# LPCB234_-_PSU.net
KiCad netlist of a schematic drawn in Altium Designer
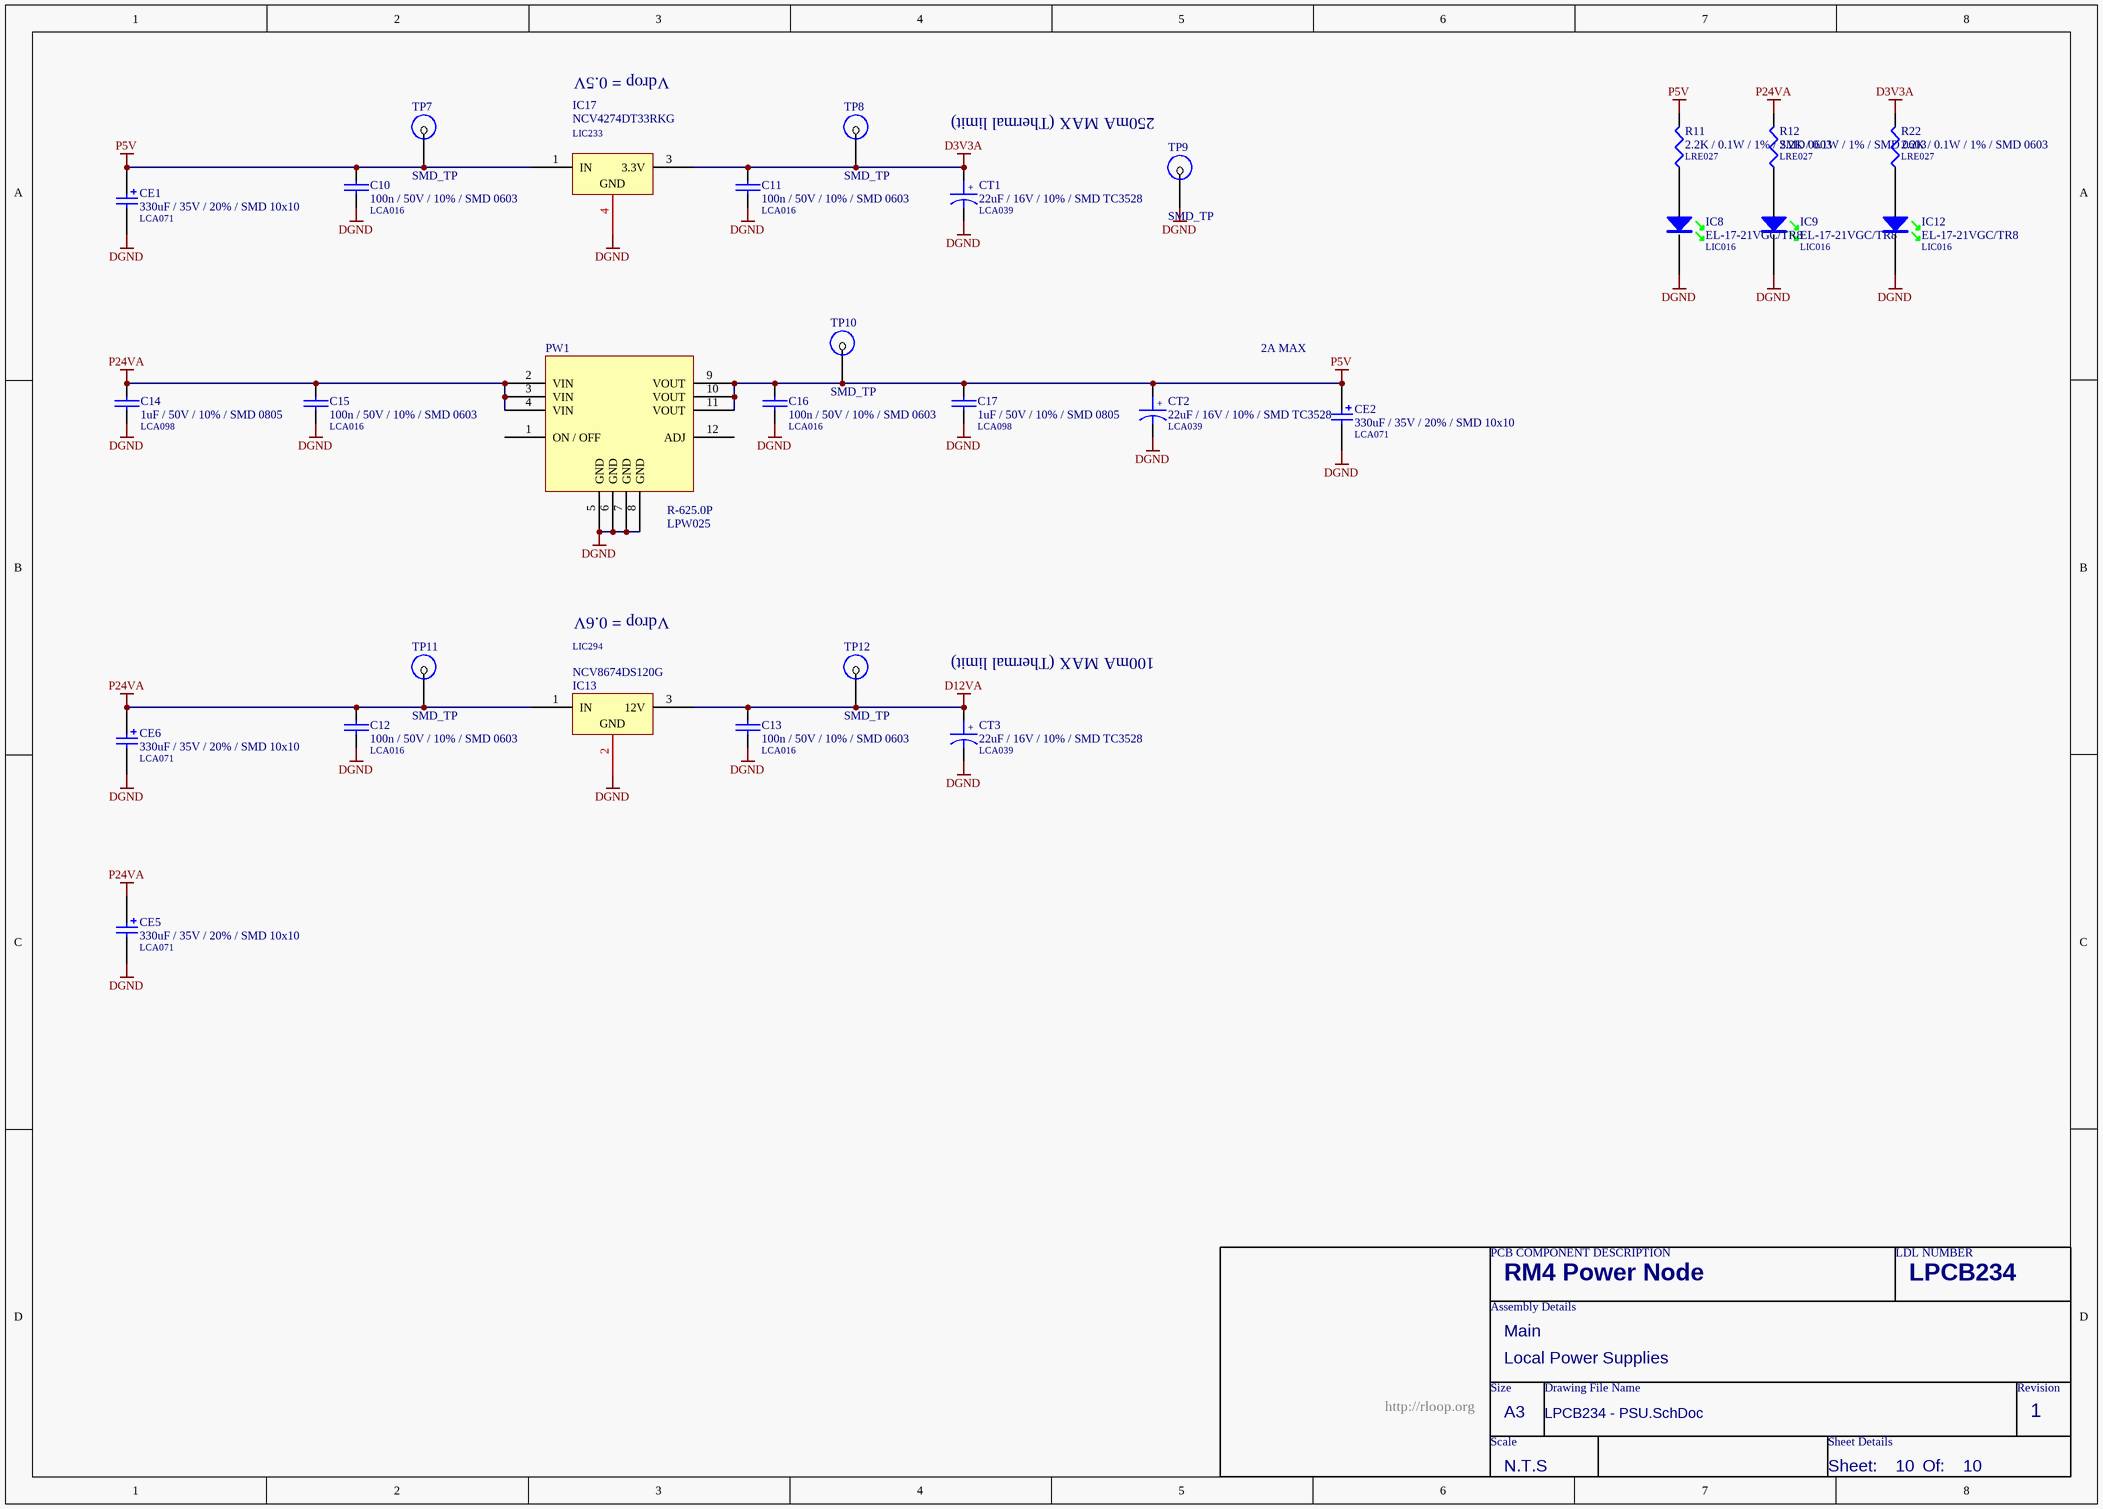
[diagram p0: LPCB234 - PSU.SchDoc]

(export (version "E")
  (design (tool "Eeschema 10.0.6"))
  (components
    (comp (ref "C10")
      (value "100n / 50V / 10% / SMD 0603")
      (footprint "LFP011__CC1608-0603-IPC7351_B")
      (description "Capacitor, Ceramic Chip, 100nF (0.1uF), 50V, 5%, SMD 0603 [LCA016]")
      (fields (field (name "LDL_NUMBER") "LCA016"))
      (libsource (lib "LDL_Capacitors") (part "100n / 50V / 10% / SMD 0603"))
    )
    (comp (ref "C11")
      (value "100n / 50V / 10% / SMD 0603")
      (footprint "LFP011__CC1608-0603-IPC7351_B")
      (description "Capacitor, Ceramic Chip, 100nF (0.1uF), 50V, 5%, SMD 0603 [LCA016]")
      (fields (field (name "LDL_NUMBER") "LCA016"))
      (libsource (lib "LDL_Capacitors") (part "100n / 50V / 10% / SMD 0603"))
    )
    (comp (ref "C12")
      (value "100n / 50V / 10% / SMD 0603")
      (footprint "LFP011__CC1608-0603-IPC7351_B")
      (description "Capacitor, Ceramic Chip, 100nF (0.1uF), 50V, 5%, SMD 0603 [LCA016]")
      (fields (field (name "LDL_NUMBER") "LCA016"))
      (libsource (lib "LDL_Capacitors") (part "100n / 50V / 10% / SMD 0603"))
    )
    (comp (ref "C13")
      (value "100n / 50V / 10% / SMD 0603")
      (footprint "LFP011__CC1608-0603-IPC7351_B")
      (description "Capacitor, Ceramic Chip, 100nF (0.1uF), 50V, 5%, SMD 0603 [LCA016]")
      (fields (field (name "LDL_NUMBER") "LCA016"))
      (libsource (lib "LDL_Capacitors") (part "100n / 50V / 10% / SMD 0603"))
    )
    (comp (ref "C14")
      (value "1uF / 50V / 10% / SMD 0805")
      (footprint "LFP010__CC2012-0805-IPC7351_B")
      (description "Capacitor, Ceramic Chip, 1uF, 50V, SMD 0805 [LCA098]")
      (fields (field (name "LDL_NUMBER") "LCA098"))
      (libsource (lib "LDL_Capacitors") (part "1uF / 50V / 10% / SMD 0805"))
    )
    (comp (ref "C15")
      (value "100n / 50V / 10% / SMD 0603")
      (footprint "LFP011__CC1608-0603-IPC7351_B")
      (description "Capacitor, Ceramic Chip, 100nF (0.1uF), 50V, 5%, SMD 0603 [LCA016]")
      (fields (field (name "LDL_NUMBER") "LCA016"))
      (libsource (lib "LDL_Capacitors") (part "100n / 50V / 10% / SMD 0603"))
    )
    (comp (ref "C16")
      (value "100n / 50V / 10% / SMD 0603")
      (footprint "LFP011__CC1608-0603-IPC7351_B")
      (description "Capacitor, Ceramic Chip, 100nF (0.1uF), 50V, 5%, SMD 0603 [LCA016]")
      (fields (field (name "LDL_NUMBER") "LCA016"))
      (libsource (lib "LDL_Capacitors") (part "100n / 50V / 10% / SMD 0603"))
    )
    (comp (ref "C17")
      (value "1uF / 50V / 10% / SMD 0805")
      (footprint "LFP010__CC2012-0805-IPC7351_B")
      (description "Capacitor, Ceramic Chip, 1uF, 50V, SMD 0805 [LCA098]")
      (fields (field (name "LDL_NUMBER") "LCA098"))
      (libsource (lib "LDL_Capacitors") (part "1uF / 50V / 10% / SMD 0805"))
    )
    (comp (ref "CE1")
      (value "330uF / 35V / 20% / SMD 10x10")
      (footprint "LFP041__NICHICON_WT_10X10")
      (description "Capacitor, Aluminum Electrolytic, 330uF, 35V, 20%, SMD (10mm x 10mm) [LCA071]")
      (fields (field (name "LDL_NUMBER") "LCA071"))
      (libsource (lib "LDL_Capacitors") (part "330uF / 35V / 20% / SMD 10x10"))
    )
    (comp (ref "CE2")
      (value "330uF / 35V / 20% / SMD 10x10")
      (footprint "LFP041__NICHICON_WT_10X10")
      (description "Capacitor, Aluminum Electrolytic, 330uF, 35V, 20%, SMD (10mm x 10mm) [LCA071]")
      (fields (field (name "LDL_NUMBER") "LCA071"))
      (libsource (lib "LDL_Capacitors") (part "330uF / 35V / 20% / SMD 10x10"))
    )
    (comp (ref "CE5")
      (value "330uF / 35V / 20% / SMD 10x10")
      (footprint "LFP041__NICHICON_WT_10X10")
      (description "Capacitor, Aluminum Electrolytic, 330uF, 35V, 20%, SMD (10mm x 10mm) [LCA071]")
      (fields (field (name "LDL_NUMBER") "LCA071"))
      (libsource (lib "LDL_Capacitors") (part "330uF / 35V / 20% / SMD 10x10"))
    )
    (comp (ref "CE6")
      (value "330uF / 35V / 20% / SMD 10x10")
      (footprint "LFP041__NICHICON_WT_10X10")
      (description "Capacitor, Aluminum Electrolytic, 330uF, 35V, 20%, SMD (10mm x 10mm) [LCA071]")
      (fields (field (name "LDL_NUMBER") "LCA071"))
      (libsource (lib "LDL_Capacitors") (part "330uF / 35V / 20% / SMD 10x10"))
    )
    (comp (ref "CT1")
      (value "22uF / 16V / 10% / SMD TC3528")
      (footprint "LFP018__TC3528")
      (description "Capacitor, Tantalum, 22uF, 16V, 10%, SMD TC3528 (BCASE) [LCA039]")
      (fields (field (name "LDL_NUMBER") "LCA039"))
      (libsource (lib "LDL_Capacitors") (part "22uF / 16V / 10% / SMD TC3528"))
    )
    (comp (ref "CT2")
      (value "22uF / 16V / 10% / SMD TC3528")
      (footprint "LFP018__TC3528")
      (description "Capacitor, Tantalum, 22uF, 16V, 10%, SMD TC3528 (BCASE) [LCA039]")
      (fields (field (name "LDL_NUMBER") "LCA039"))
      (libsource (lib "LDL_Capacitors") (part "22uF / 16V / 10% / SMD TC3528"))
    )
    (comp (ref "CT3")
      (value "22uF / 16V / 10% / SMD TC3528")
      (footprint "LFP018__TC3528")
      (description "Capacitor, Tantalum, 22uF, 16V, 10%, SMD TC3528 (BCASE) [LCA039]")
      (fields (field (name "LDL_NUMBER") "LCA039"))
      (libsource (lib "LDL_Capacitors") (part "22uF / 16V / 10% / SMD TC3528"))
    )
    (comp (ref "IC8")
      (value "EL-17-21VGC/TR8")
      (footprint "CR2012-0805-LED")
      (description "LED, SMD, 0805 Green [LIC016]")
      (fields (field (name "LDL_NUMBER") "LIC016"))
      (libsource (lib "LDL_Semiconductors") (part "EL-17-21VGC/TR8"))
    )
    (comp (ref "IC9")
      (value "EL-17-21VGC/TR8")
      (footprint "CR2012-0805-LED")
      (description "LED, SMD, 0805 Green [LIC016]")
      (fields (field (name "LDL_NUMBER") "LIC016"))
      (libsource (lib "LDL_Semiconductors") (part "EL-17-21VGC/TR8"))
    )
    (comp (ref "IC12")
      (value "EL-17-21VGC/TR8")
      (footprint "CR2012-0805-LED")
      (description "LED, SMD, 0805 Green [LIC016]")
      (fields (field (name "LDL_NUMBER") "LIC016"))
      (libsource (lib "LDL_Semiconductors") (part "EL-17-21VGC/TR8"))
    )
    (comp (ref "IC13")
      (value "NCV8674DS120G")
      (footprint "LFP082__D2PAK")
      (description "IC, Voltage Regulator, 0.35A, 12V, SMD D2PAK [LIC294]")
      (fields (field (name "LDL_NUMBER") "LIC294"))
      (libsource (lib "LDL_Semiconductors") (part "NCV8674DS120G"))
    )
    (comp (ref "IC17")
      (value "NCV4274DT33RKG")
      (footprint "LFP019__369A-13")
      (description "IC, Voltage Regulator, 400mA, 3.3V LDO, SMD DPAK [LIC233]")
      (fields (field (name "LDL_NUMBER") "LIC233"))
      (libsource (lib "LDL_Semiconductors") (part "NCV4274DT33RKG"))
    )
    (comp (ref "PW1")
      (value "R-625.0P")
      (footprint "R-625.0P")
      (description "Non Isolated DC/DC Module")
      (fields (field (name "LDL_NUMBER") "LPW025"))
      (libsource (lib "LDL_Power") (part "R-625.0P"))
    )
    (comp (ref "R11")
      (value "2.2K / 0.1W / 1% / SMD 0603")
      (footprint "LFP020__CR1608-0603-IPC7351_B")
      (description "Resistor, Ceramic Chip, 2.2K, 0.1W, 1%, SMD 0603 [LRE027]")
      (fields (field (name "LDL_NUMBER") "LRE027"))
      (libsource (lib "LDL_Resistors") (part "2.2K / 0.1W / 1% / SMD 0603"))
    )
    (comp (ref "R12")
      (value "2.2K / 0.1W / 1% / SMD 0603")
      (footprint "LFP020__CR1608-0603-IPC7351_B")
      (description "Resistor, Ceramic Chip, 2.2K, 0.1W, 1%, SMD 0603 [LRE027]")
      (fields (field (name "LDL_NUMBER") "LRE027"))
      (libsource (lib "LDL_Resistors") (part "2.2K / 0.1W / 1% / SMD 0603"))
    )
    (comp (ref "R22")
      (value "2.2K / 0.1W / 1% / SMD 0603")
      (footprint "LFP020__CR1608-0603-IPC7351_B")
      (description "Resistor, Ceramic Chip, 2.2K, 0.1W, 1%, SMD 0603 [LRE027]")
      (fields (field (name "LDL_NUMBER") "LRE027"))
      (libsource (lib "LDL_Resistors") (part "2.2K / 0.1W / 1% / SMD 0603"))
    )
    (comp (ref "TP7")
      (value "SMD_TP")
      (footprint "SMD-TP")
      (description "SMD Test Point")
      (libsource (lib "LDL_Connectors") (part "SMD_TP"))
    )
    (comp (ref "TP8")
      (value "SMD_TP")
      (footprint "SMD-TP")
      (description "SMD Test Point")
      (libsource (lib "LDL_Connectors") (part "SMD_TP"))
    )
    (comp (ref "TP9")
      (value "SMD_TP")
      (footprint "SMD-TP")
      (description "SMD Test Point")
      (libsource (lib "LDL_Connectors") (part "SMD_TP"))
    )
    (comp (ref "TP10")
      (value "SMD_TP")
      (footprint "SMD-TP")
      (description "SMD Test Point")
      (libsource (lib "LDL_Connectors") (part "SMD_TP"))
    )
    (comp (ref "TP11")
      (value "SMD_TP")
      (footprint "SMD-TP")
      (description "SMD Test Point")
      (libsource (lib "LDL_Connectors") (part "SMD_TP"))
    )
    (comp (ref "TP12")
      (value "SMD_TP")
      (footprint "SMD-TP")
      (description "SMD Test Point")
      (libsource (lib "LDL_Connectors") (part "SMD_TP"))
    )
  )
  (nets
    (net (code "1") (name "D3V3A") (class "Default")
      (node (ref "C11") (pin "1") (pintype "passive"))
      (node (ref "CT1") (pin "1") (pinfunction "1_1") (pintype "passive"))
      (node (ref "IC17") (pin "3") (pinfunction "3.3V_3") (pintype "power_in"))
      (node (ref "R22") (pin "2") (pintype "passive"))
      (node (ref "TP8") (pin "1") (pintype "passive"))
    )
    (net (code "2") (name "D12VA") (class "Default")
      (node (ref "C13") (pin "1") (pintype "passive"))
      (node (ref "CT3") (pin "1") (pinfunction "1_1") (pintype "passive"))
      (node (ref "IC13") (pin "3") (pinfunction "12V_3") (pintype "power_in"))
      (node (ref "TP12") (pin "1") (pintype "passive"))
    )
    (net (code "3") (name "DGND") (class "Default")
      (node (ref "C10") (pin "2") (pintype "passive"))
      (node (ref "C11") (pin "2") (pintype "passive"))
      (node (ref "C12") (pin "2") (pintype "passive"))
      (node (ref "C13") (pin "2") (pintype "passive"))
      (node (ref "C14") (pin "2") (pintype "passive"))
      (node (ref "C15") (pin "2") (pintype "passive"))
      (node (ref "C16") (pin "2") (pintype "passive"))
      (node (ref "C17") (pin "2") (pintype "passive"))
      (node (ref "CE1") (pin "2") (pinfunction "2_2") (pintype "passive"))
      (node (ref "CE2") (pin "2") (pinfunction "2_2") (pintype "passive"))
      (node (ref "CE5") (pin "2") (pinfunction "2_2") (pintype "passive"))
      (node (ref "CE6") (pin "2") (pinfunction "2_2") (pintype "passive"))
      (node (ref "CT1") (pin "2") (pinfunction "2_2") (pintype "passive"))
      (node (ref "CT2") (pin "2") (pinfunction "2_2") (pintype "passive"))
      (node (ref "CT3") (pin "2") (pinfunction "2_2") (pintype "passive"))
      (node (ref "IC12") (pin "K") (pintype "passive"))
      (node (ref "IC13") (pin "2") (pinfunction "GND_2") (pintype "power_in"))
      (node (ref "IC17") (pin "4") (pinfunction "GND_4") (pintype "power_in"))
      (node (ref "IC8") (pin "K") (pintype "passive"))
      (node (ref "IC9") (pin "K") (pintype "passive"))
      (node (ref "PW1") (pin "5") (pinfunction "GND_5") (pintype "power_in"))
      (node (ref "PW1") (pin "6") (pinfunction "GND_6") (pintype "power_in"))
      (node (ref "PW1") (pin "7") (pinfunction "GND_7") (pintype "power_in"))
      (node (ref "PW1") (pin "8") (pinfunction "GND_8") (pintype "power_in"))
      (node (ref "TP9") (pin "1") (pintype "passive"))
    )
    (net (code "4") (name "Net-(IC8-PadA)") (class "Default")
      (node (ref "IC8") (pin "A") (pintype "passive"))
      (node (ref "R11") (pin "1") (pintype "passive"))
    )
    (net (code "5") (name "Net-(IC9-PadA)") (class "Default")
      (node (ref "IC9") (pin "A") (pintype "passive"))
      (node (ref "R12") (pin "1") (pintype "passive"))
    )
    (net (code "6") (name "Net-(IC12-PadA)") (class "Default")
      (node (ref "IC12") (pin "A") (pintype "passive"))
      (node (ref "R22") (pin "1") (pintype "passive"))
    )
    (net (code "7") (name "P5V") (class "Default")
      (node (ref "C10") (pin "1") (pintype "passive"))
      (node (ref "C16") (pin "1") (pintype "passive"))
      (node (ref "C17") (pin "1") (pintype "passive"))
      (node (ref "CE1") (pin "1") (pinfunction "1_1") (pintype "passive"))
      (node (ref "CE2") (pin "1") (pinfunction "1_1") (pintype "passive"))
      (node (ref "CT2") (pin "1") (pinfunction "1_1") (pintype "passive"))
      (node (ref "IC17") (pin "1") (pinfunction "IN_1") (pintype "power_in"))
      (node (ref "PW1") (pin "10") (pinfunction "VOUT_10") (pintype "power_in"))
      (node (ref "PW1") (pin "11") (pinfunction "VOUT_11") (pintype "power_in"))
      (node (ref "PW1") (pin "9") (pinfunction "VOUT_9") (pintype "power_in"))
      (node (ref "R11") (pin "2") (pintype "passive"))
      (node (ref "TP10") (pin "1") (pintype "passive"))
      (node (ref "TP7") (pin "1") (pintype "passive"))
    )
    (net (code "8") (name "P24VA") (class "Default")
      (node (ref "C12") (pin "1") (pintype "passive"))
      (node (ref "C14") (pin "1") (pintype "passive"))
      (node (ref "C15") (pin "1") (pintype "passive"))
      (node (ref "CE5") (pin "1") (pinfunction "1_1") (pintype "passive"))
      (node (ref "CE6") (pin "1") (pinfunction "1_1") (pintype "passive"))
      (node (ref "IC13") (pin "1") (pinfunction "IN_1") (pintype "power_in"))
      (node (ref "PW1") (pin "2") (pinfunction "VIN_2") (pintype "power_in"))
      (node (ref "PW1") (pin "3") (pinfunction "VIN_3") (pintype "power_in"))
      (node (ref "PW1") (pin "4") (pinfunction "VIN_4") (pintype "power_in"))
      (node (ref "R12") (pin "2") (pintype "passive"))
      (node (ref "TP11") (pin "1") (pintype "passive"))
    )
    (net (code "9") (name "unconnected-(PW1-ADJ-Pad12)") (class "Default")
      (node (ref "PW1") (pin "12") (pinfunction "ADJ_12") (pintype "passive"))
    )
    (net (code "10") (name "unconnected-(PW1-ON_{slash}_OFF-Pad1)") (class "Default")
      (node (ref "PW1") (pin "1") (pinfunction "ON_/_OFF_1") (pintype "passive"))
    )
  )
)
